# WorstCaseHT.net
KiCad netlist of a schematic drawn in Altium Designer
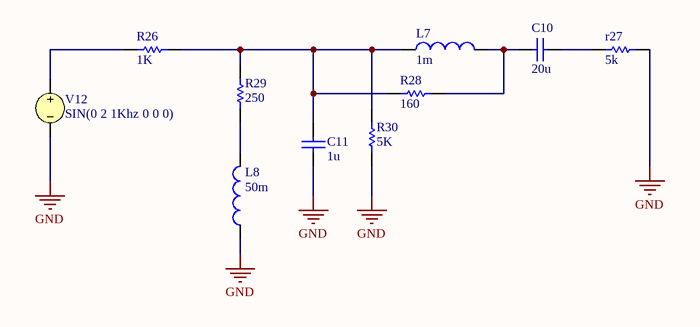
[diagram p0: WorstCaseHT.SchDoc]

(export (version "E")
  (design (tool "Eeschema 10.0.6"))
  (components
    (comp (ref "C10")
      (value "20u")
      (description "Capacitor")
      (libsource (lib "Simulation Generic Components") (part "Capacitor"))
    )
    (comp (ref "C11")
      (value "1u")
      (description "Capacitor")
      (libsource (lib "Simulation Generic Components") (part "Capacitor"))
    )
    (comp (ref "L7")
      (value "1m")
      (description "Inductor")
      (libsource (lib "Simulation Generic Components") (part "Inductor"))
    )
    (comp (ref "L8")
      (value "50m")
      (description "Inductor")
      (libsource (lib "Simulation Generic Components") (part "Inductor"))
    )
    (comp (ref "R26")
      (value "1K")
      (description "Resistor")
      (libsource (lib "Simulation Generic Components") (part "Resistor"))
    )
    (comp (ref "r27")
      (value "5k")
      (description "Resistor")
      (libsource (lib "Simulation Generic Components") (part "Resistor"))
    )
    (comp (ref "R28")
      (value "160")
      (description "Resistor")
      (libsource (lib "Simulation Generic Components") (part "Resistor"))
    )
    (comp (ref "R29")
      (value "250")
      (description "Resistor")
      (libsource (lib "Simulation Generic Components") (part "Resistor"))
    )
    (comp (ref "R30")
      (value "5K")
      (description "Resistor")
      (libsource (lib "Simulation Generic Components") (part "Resistor"))
    )
    (comp (ref "V12")
      (value "SIN(0 2 1Khz 0 0 0)")
      (description "Voltage Source")
      (fields (field (name "PUBLISHER") "Altium Limited"))
      (libsource (lib "Simulation Generic Components") (part "VSRC"))
    )
  )
  (nets
    (net (code "1") (name "GND") (class "Default")
      (node (ref "C11") (pin "1") (pinfunction "1_1") (pintype "passive"))
      (node (ref "L8") (pin "1") (pinfunction "1_1") (pintype "passive"))
      (node (ref "R30") (pin "1") (pinfunction "1_1") (pintype "passive"))
      (node (ref "V12") (pin "2") (pinfunction "2_2") (pintype "passive"))
      (node (ref "r27") (pin "1") (pinfunction "1_1") (pintype "passive"))
    )
    (net (code "2") (name "Net-(C10-Pad1)") (class "Default")
      (node (ref "C10") (pin "1") (pinfunction "1_1") (pintype "passive"))
      (node (ref "r27") (pin "2") (pinfunction "2_2") (pintype "passive"))
    )
    (net (code "3") (name "Net-(C10-Pad2)") (class "Default")
      (node (ref "C10") (pin "2") (pinfunction "2_2") (pintype "passive"))
      (node (ref "L7") (pin "2") (pinfunction "2_2") (pintype "passive"))
      (node (ref "R28") (pin "1") (pinfunction "1_1") (pintype "passive"))
    )
    (net (code "4") (name "Net-(C11-Pad2)") (class "Default")
      (node (ref "C11") (pin "2") (pinfunction "2_2") (pintype "passive"))
      (node (ref "L7") (pin "1") (pinfunction "1_1") (pintype "passive"))
      (node (ref "R26") (pin "2") (pinfunction "2_2") (pintype "passive"))
      (node (ref "R28") (pin "2") (pinfunction "2_2") (pintype "passive"))
      (node (ref "R29") (pin "2") (pinfunction "2_2") (pintype "passive"))
      (node (ref "R30") (pin "2") (pinfunction "2_2") (pintype "passive"))
    )
    (net (code "5") (name "Net-(L8-Pad2)") (class "Default")
      (node (ref "L8") (pin "2") (pinfunction "2_2") (pintype "passive"))
      (node (ref "R29") (pin "1") (pinfunction "1_1") (pintype "passive"))
    )
    (net (code "6") (name "Net-(R26-Pad1)") (class "Default")
      (node (ref "R26") (pin "1") (pinfunction "1_1") (pintype "passive"))
      (node (ref "V12") (pin "1") (pinfunction "1_1") (pintype "passive"))
    )
  )
)
